# IMU_Project.net
KiCad netlist of a schematic drawn in Altium Designer
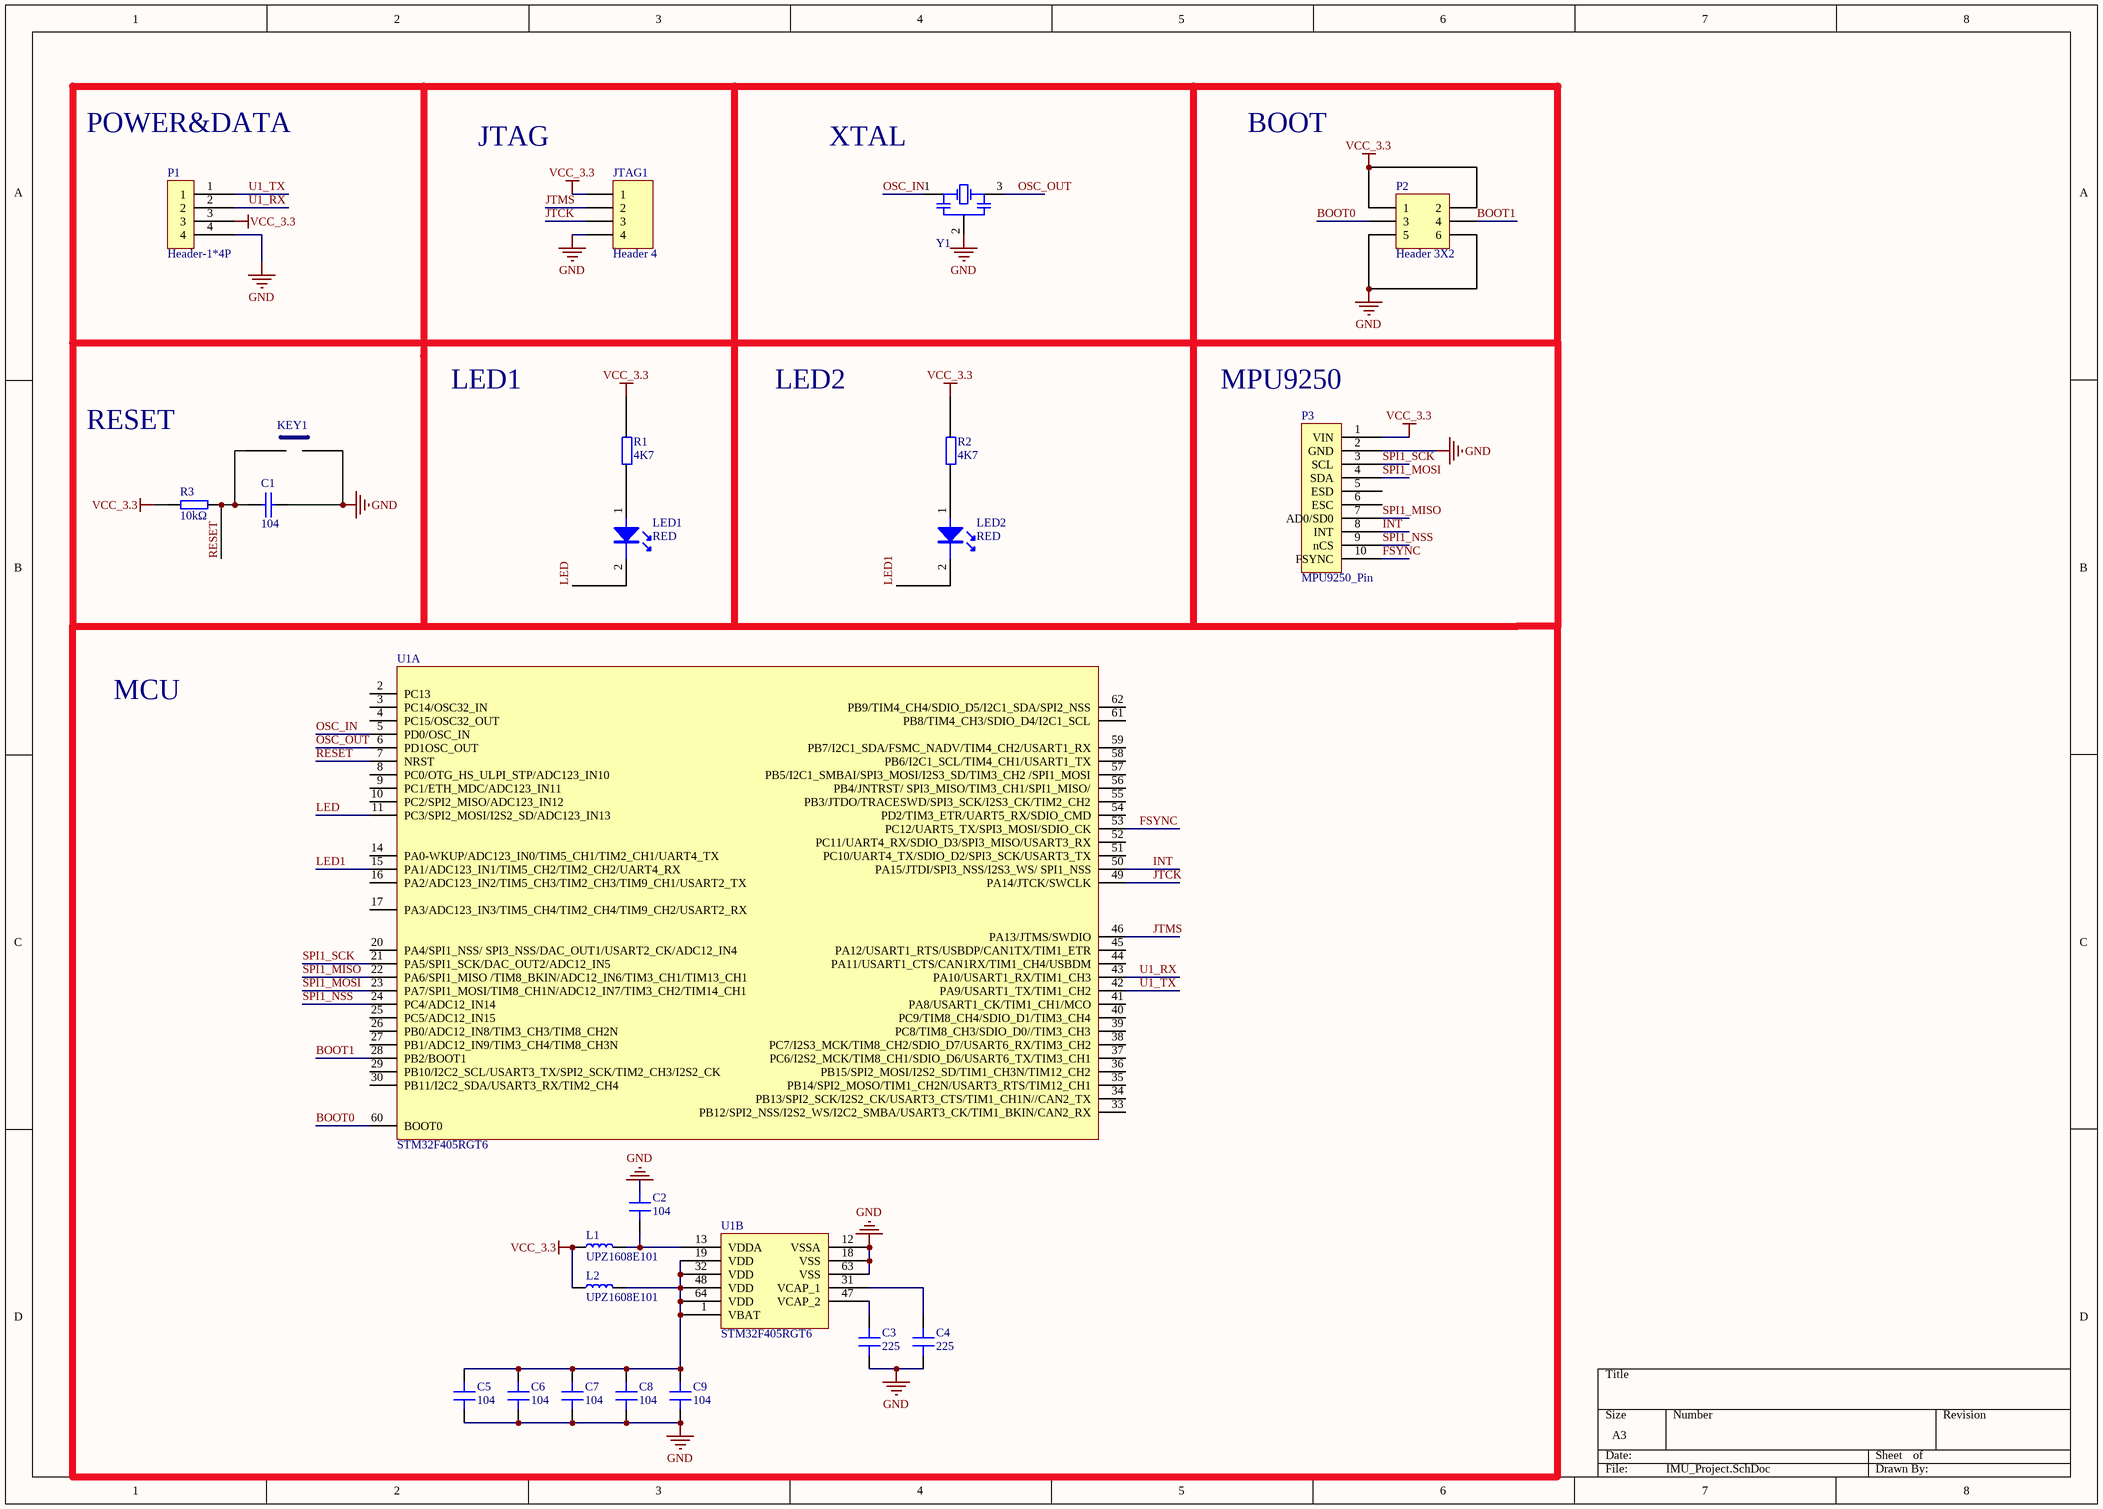
[diagram p0: IMU_Project.SchDoc]

(export (version "E")
  (design (tool "Eeschema 10.0.6"))
  (components
    (comp (ref "C1") (value "104") (footprint "C0603") (libsource (lib "main") (part "C0603")))
    (comp (ref "C2")
      (value "104")
      (footprint "C0603/1608")
      (description "陶瓷电容")
      (libsource (lib "WMJ2019_Devices") (part "陶瓷电容"))
    )
    (comp (ref "C3")
      (value "225")
      (footprint "C0603/1608")
      (description "陶瓷电容")
      (libsource (lib "WMJ2019_Devices") (part "陶瓷电容"))
    )
    (comp (ref "C4")
      (value "225")
      (footprint "C0603/1608")
      (description "陶瓷电容")
      (libsource (lib "WMJ2019_Devices") (part "陶瓷电容"))
    )
    (comp (ref "C5")
      (value "104")
      (footprint "C0603/1608")
      (description "陶瓷电容")
      (libsource (lib "WMJ2019_Devices") (part "陶瓷电容"))
    )
    (comp (ref "C6")
      (value "104")
      (footprint "C0603/1608")
      (description "陶瓷电容")
      (libsource (lib "WMJ2019_Devices") (part "陶瓷电容"))
    )
    (comp (ref "C7")
      (value "104")
      (footprint "C0603/1608")
      (description "陶瓷电容")
      (libsource (lib "WMJ2019_Devices") (part "陶瓷电容"))
    )
    (comp (ref "C8")
      (value "104")
      (footprint "C0603/1608")
      (description "陶瓷电容")
      (libsource (lib "WMJ2019_Devices") (part "陶瓷电容"))
    )
    (comp (ref "C9")
      (value "104")
      (footprint "C0603/1608")
      (description "陶瓷电容")
      (libsource (lib "WMJ2019_Devices") (part "陶瓷电容"))
    )
    (comp (ref "JTAG1")
      (value "Header 4")
      (footprint "Header1*4_XH2.54_zhi")
      (description "Header, 4-Pin")
      (fields (field (name "PUBLISHER") "Altium Limited"))
      (libsource (lib "Miscellaneous Connectors") (part "Header 4"))
    )
    (comp (ref "KEY1") (value "KEY2") (footprint "KEY_RESET") (libsource (lib "library-1") (part "KEY")))
    (comp (ref "L1")
      (value "UPZ1608E101")
      (footprint "L0603/1608")
      (description "贴片磁珠")
      (libsource (lib "WMJ2019_Devices") (part "磁珠"))
    )
    (comp (ref "L2")
      (value "UPZ1608E101")
      (footprint "L0603/1608")
      (description "贴片磁珠")
      (libsource (lib "WMJ2019_Devices") (part "磁珠"))
    )
    (comp (ref "LED1")
      (value "LED RED")
      (footprint "LED0603")
      (fields (field (name "COLOR") "RED"))
      (libsource (lib "Rescue") (part "LED"))
    )
    (comp (ref "LED2")
      (value "LED RED")
      (footprint "LED0603")
      (fields (field (name "COLOR") "RED"))
      (libsource (lib "Rescue") (part "LED"))
    )
    (comp (ref "P1")
      (value "Header-1*4P")
      (footprint "Header1*4_XH2.54_Lie")
      (description "单排4P排针")
      (libsource (lib "WMJ2019_Connectors") (part "Header-1*4P"))
    )
    (comp (ref "P2")
      (value "Header 3X2")
      (footprint "BOOT")
      (description "Header, 3-Pin, Dual row")
      (fields (field (name "PUBLISHER") "Altium Limited"))
      (libsource (lib "PCB_Project") (part "Header 3X2"))
    )
    (comp (ref "P3")
      (value "MPU9250_Pin")
      (footprint "MPU9250_Pin")
      (libsource (lib "MPU9250") (part "MPU9250_Pin"))
    )
    (comp (ref "R1") (value "4K7") (footprint "R0603") (libsource (lib "Rescue") (part "Resistor")))
    (comp (ref "R2") (value "4K7") (footprint "R0603") (libsource (lib "Rescue") (part "Resistor")))
    (comp (ref "R3") (value "10kΩ") (footprint "R0603") (libsource (lib "main") (part "RES_WYN")))
    (comp (ref "U1")
      (value "STM32F405RGT6")
      (footprint "LQFP64")
      (description "微控制器STM32F405RGT6")
      (libsource (lib "WMJ2019_MCU") (part "STM32F405RGT6"))
    )
    (comp (ref "Y1")
      (value "Crystal_Cap")
      (footprint "XTAL-3213")
      (fields (field (name "PUBLISHER") "Altium Limited"))
      (libsource (lib "chassis_PCB_Project") (part "Crystal_Cap"))
    )
  )
  (nets
    (net (code "1") (name "/BOOT0") (class "Default")
      (node (ref "P2") (pin "3") (pinfunction "3_3") (pintype "passive"))
      (node (ref "U1") (pin "60") (pinfunction "BOOT0_60") (pintype "passive"))
    )
    (net (code "2") (name "/BOOT1") (class "Default")
      (node (ref "P2") (pin "4") (pinfunction "4_4") (pintype "passive"))
      (node (ref "U1") (pin "28") (pinfunction "PB2/BOOT1_28") (pintype "passive"))
    )
    (net (code "3") (name "/FSYNC") (class "Default")
      (node (ref "P3") (pin "10") (pinfunction "FSYNC_10") (pintype "passive"))
      (node (ref "U1") (pin "53") (pinfunction "PC12/UART5_TX/SPI3_MOSI/SDIO_CK_53") (pintype "passive"))
    )
    (net (code "4") (name "/INT") (class "Default")
      (node (ref "P3") (pin "8") (pinfunction "INT_8") (pintype "passive"))
      (node (ref "U1") (pin "50") (pinfunction "PA15/JTDI/SPI3_NSS/I2S3_WS/_SPI1_NSS_50") (pintype "passive"))
    )
    (net (code "5") (name "/JTCK") (class "Default")
      (node (ref "JTAG1") (pin "3") (pinfunction "3_3") (pintype "passive"))
      (node (ref "U1") (pin "49") (pinfunction "PA14/JTCK/SWCLK_49") (pintype "passive"))
    )
    (net (code "6") (name "/JTMS") (class "Default")
      (node (ref "JTAG1") (pin "2") (pinfunction "2_2") (pintype "passive"))
      (node (ref "U1") (pin "46") (pinfunction "PA13/JTMS/SWDIO_46") (pintype "passive"))
    )
    (net (code "7") (name "/LED") (class "Default")
      (node (ref "LED1") (pin "2") (pinfunction "K_2") (pintype "passive"))
      (node (ref "U1") (pin "11") (pinfunction "PC3/SPI2_MOSI/I2S2_SD/ADC123_IN13_11") (pintype "passive"))
    )
    (net (code "8") (name "/LED1") (class "Default")
      (node (ref "LED2") (pin "2") (pinfunction "K_2") (pintype "passive"))
      (node (ref "U1") (pin "15") (pinfunction "PA1/ADC123_IN1/TIM5_CH2/TIM2_CH2/UART4_RX_15") (pintype "passive"))
    )
    (net (code "9") (name "/OSC_IN") (class "Default")
      (node (ref "U1") (pin "5") (pinfunction "PD0/OSC_IN_5") (pintype "passive"))
      (node (ref "Y1") (pin "1") (pinfunction "OSC1_1") (pintype "passive"))
    )
    (net (code "10") (name "/OSC_OUT") (class "Default")
      (node (ref "U1") (pin "6") (pinfunction "PD1OSC_OUT_6") (pintype "passive"))
      (node (ref "Y1") (pin "3") (pinfunction "OSC3_3") (pintype "passive"))
    )
    (net (code "11") (name "/RESET") (class "Default")
      (node (ref "C1") (pin "1") (pintype "passive"))
      (node (ref "KEY1") (pin "2") (pinfunction "2_2") (pintype "passive"))
      (node (ref "R3") (pin "1") (pinfunction "1_1") (pintype "passive"))
      (node (ref "U1") (pin "7") (pinfunction "NRST_7") (pintype "passive"))
    )
    (net (code "12") (name "/SPI1_MISO") (class "Default")
      (node (ref "P3") (pin "7") (pinfunction "AD0/SD0_7") (pintype "passive"))
      (node (ref "U1") (pin "22") (pinfunction "PA6/SPI1_MISO_/TIM8_BKIN/ADC12_IN6/TIM3_CH1/TIM13_CH1_22") (pintype "passive"))
    )
    (net (code "13") (name "/SPI1_MOSI") (class "Default")
      (node (ref "P3") (pin "4") (pinfunction "SDA_4") (pintype "passive"))
      (node (ref "U1") (pin "23") (pinfunction "PA7/SPI1_MOSI/TIM8_CH1N/ADC12_IN7/TIM3_CH2/TIM14_CH1_23") (pintype "passive"))
    )
    (net (code "14") (name "/SPI1_NSS") (class "Default")
      (node (ref "P3") (pin "9") (pinfunction "nCS_9") (pintype "passive"))
      (node (ref "U1") (pin "24") (pinfunction "PC4/ADC12_IN14_24") (pintype "passive"))
    )
    (net (code "15") (name "/SPI1_SCK") (class "Default")
      (node (ref "P3") (pin "3") (pinfunction "SCL_3") (pintype "passive"))
      (node (ref "U1") (pin "21") (pinfunction "PA5/SPI1_SCK/DAC_OUT2/ADC12_IN5_21") (pintype "passive"))
    )
    (net (code "16") (name "/U1_RX") (class "Default")
      (node (ref "P1") (pin "2") (pinfunction "2_2") (pintype "passive"))
      (node (ref "U1") (pin "43") (pinfunction "PA10/USART1_RX/TIM1_CH3_43") (pintype "passive"))
    )
    (net (code "17") (name "/U1_TX") (class "Default")
      (node (ref "P1") (pin "1") (pinfunction "1_1") (pintype "passive"))
      (node (ref "U1") (pin "42") (pinfunction "PA9/USART1_TX/TIM1_CH2_42") (pintype "passive"))
    )
    (net (code "18") (name "GND") (class "Default")
      (node (ref "C1") (pin "2") (pintype "passive"))
      (node (ref "C2") (pin "2") (pintype "passive"))
      (node (ref "C3") (pin "1") (pintype "passive"))
      (node (ref "C4") (pin "1") (pintype "passive"))
      (node (ref "C5") (pin "1") (pintype "passive"))
      (node (ref "C6") (pin "1") (pintype "passive"))
      (node (ref "C7") (pin "1") (pintype "passive"))
      (node (ref "C8") (pin "1") (pintype "passive"))
      (node (ref "C9") (pin "1") (pintype "passive"))
      (node (ref "JTAG1") (pin "4") (pinfunction "4_4") (pintype "passive"))
      (node (ref "KEY1") (pin "1") (pinfunction "1_1") (pintype "passive"))
      (node (ref "P1") (pin "4") (pinfunction "4_4") (pintype "passive"))
      (node (ref "P2") (pin "5") (pinfunction "5_5") (pintype "passive"))
      (node (ref "P2") (pin "6") (pinfunction "6_6") (pintype "passive"))
      (node (ref "P3") (pin "2") (pinfunction "GND_2") (pintype "passive"))
      (node (ref "U1") (pin "12") (pinfunction "VSSA_12") (pintype "passive"))
      (node (ref "U1") (pin "18") (pinfunction "VSS_18") (pintype "passive"))
      (node (ref "U1") (pin "63") (pinfunction "VSS_63") (pintype "passive"))
      (node (ref "Y1") (pin "2") (pinfunction "OSC2_2") (pintype "passive"))
    )
    (net (code "19") (name "Net-(LED1-A)") (class "Default")
      (node (ref "LED1") (pin "1") (pinfunction "A_1") (pintype "passive"))
      (node (ref "R1") (pin "1") (pintype "passive"))
    )
    (net (code "20") (name "Net-(LED2-A)") (class "Default")
      (node (ref "LED2") (pin "1") (pinfunction "A_1") (pintype "passive"))
      (node (ref "R2") (pin "1") (pintype "passive"))
    )
    (net (code "21") (name "Net-(U1B-VBAT)") (class "Default")
      (node (ref "C5") (pin "2") (pintype "passive"))
      (node (ref "C6") (pin "2") (pintype "passive"))
      (node (ref "C7") (pin "2") (pintype "passive"))
      (node (ref "C8") (pin "2") (pintype "passive"))
      (node (ref "C9") (pin "2") (pintype "passive"))
      (node (ref "L2") (pin "2") (pinfunction "2_2") (pintype "passive"))
      (node (ref "U1") (pin "1") (pinfunction "VBAT_1") (pintype "passive"))
      (node (ref "U1") (pin "19") (pinfunction "VDD_19") (pintype "passive"))
      (node (ref "U1") (pin "32") (pinfunction "VDD_32") (pintype "passive"))
      (node (ref "U1") (pin "48") (pinfunction "VDD_48") (pintype "passive"))
      (node (ref "U1") (pin "64") (pinfunction "VDD_64") (pintype "passive"))
    )
    (net (code "22") (name "Net-(U1B-VCAP_1)") (class "Default")
      (node (ref "C4") (pin "2") (pintype "passive"))
      (node (ref "U1") (pin "31") (pinfunction "VCAP_1_31") (pintype "passive"))
    )
    (net (code "23") (name "Net-(U1B-VCAP_2)") (class "Default")
      (node (ref "C3") (pin "2") (pintype "passive"))
      (node (ref "U1") (pin "47") (pinfunction "VCAP_2_47") (pintype "passive"))
    )
    (net (code "24") (name "Net-(U1B-VDDA)") (class "Default")
      (node (ref "C2") (pin "1") (pintype "passive"))
      (node (ref "L1") (pin "2") (pinfunction "2_2") (pintype "passive"))
      (node (ref "U1") (pin "13") (pinfunction "VDDA_13") (pintype "passive"))
    )
    (net (code "25") (name "VCC_3.3") (class "Default")
      (node (ref "JTAG1") (pin "1") (pinfunction "1_1") (pintype "passive"))
      (node (ref "L1") (pin "1") (pinfunction "1_1") (pintype "passive"))
      (node (ref "L2") (pin "1") (pinfunction "1_1") (pintype "passive"))
      (node (ref "P1") (pin "3") (pinfunction "3_3") (pintype "passive"))
      (node (ref "P2") (pin "1") (pinfunction "1_1") (pintype "passive"))
      (node (ref "P2") (pin "2") (pinfunction "2_2") (pintype "passive"))
      (node (ref "P3") (pin "1") (pinfunction "VIN_1") (pintype "passive"))
      (node (ref "R1") (pin "2") (pintype "passive"))
      (node (ref "R2") (pin "2") (pintype "passive"))
      (node (ref "R3") (pin "2") (pinfunction "2_2") (pintype "passive"))
    )
    (net (code "26") (name "unconnected-(P3-ESC-Pad6)") (class "Default")
      (node (ref "P3") (pin "6") (pinfunction "ESC_6") (pintype "passive"))
    )
    (net (code "27") (name "unconnected-(P3-ESD-Pad5)") (class "Default")
      (node (ref "P3") (pin "5") (pinfunction "ESD_5") (pintype "passive"))
    )
    (net (code "28") (name "unconnected-(U1A-PA0-WKUP{slash}ADC123_IN0{slash}TIM5_CH1{slash}TIM2_CH1{slash}UART4_TX-Pad14)") (class "Default")
      (node (ref "U1") (pin "14") (pinfunction "PA0-WKUP/ADC123_IN0/TIM5_CH1/TIM2_CH1/UART4_TX_14") (pintype "passive"))
    )
    (net (code "29") (name "unconnected-(U1A-PA2{slash}ADC123_IN2{slash}TIM5_CH3{slash}TIM2_CH3{slash}TIM9_CH1{slash}USART2_TX-Pad16)") (class "Default")
      (node (ref "U1") (pin "16") (pinfunction "PA2/ADC123_IN2/TIM5_CH3/TIM2_CH3/TIM9_CH1/USART2_TX_16") (pintype "passive"))
    )
    (net (code "30") (name "unconnected-(U1A-PA3{slash}ADC123_IN3{slash}TIM5_CH4{slash}TIM2_CH4{slash}TIM9_CH2{slash}USART2_RX-Pad17)") (class "Default")
      (node (ref "U1") (pin "17") (pinfunction "PA3/ADC123_IN3/TIM5_CH4/TIM2_CH4/TIM9_CH2/USART2_RX_17") (pintype "passive"))
    )
    (net (code "31") (name "unconnected-(U1A-PA4{slash}SPI1_NSS{slash}_SPI3_NSS{slash}DAC_OUT1{slash}USART2_CK{slash}ADC12_IN4-Pad20)") (class "Default")
      (node (ref "U1") (pin "20") (pinfunction "PA4/SPI1_NSS/_SPI3_NSS/DAC_OUT1/USART2_CK/ADC12_IN4_20") (pintype "passive"))
    )
    (net (code "32") (name "unconnected-(U1A-PA8{slash}USART1_CK{slash}TIM1_CH1{slash}MCO-Pad41)") (class "Default")
      (node (ref "U1") (pin "41") (pinfunction "PA8/USART1_CK/TIM1_CH1/MCO_41") (pintype "passive"))
    )
    (net (code "33") (name "unconnected-(U1A-PA11{slash}USART1_CTS{slash}CAN1RX{slash}TIM1_CH4{slash}USBDM-Pad44)") (class "Default")
      (node (ref "U1") (pin "44") (pinfunction "PA11/USART1_CTS/CAN1RX/TIM1_CH4/USBDM_44") (pintype "passive"))
    )
    (net (code "34") (name "unconnected-(U1A-PA12{slash}USART1_RTS{slash}USBDP{slash}CAN1TX{slash}TIM1_ETR-Pad45)") (class "Default")
      (node (ref "U1") (pin "45") (pinfunction "PA12/USART1_RTS/USBDP/CAN1TX/TIM1_ETR_45") (pintype "passive"))
    )
    (net (code "35") (name "unconnected-(U1A-PB0{slash}ADC12_IN8{slash}TIM3_CH3{slash}TIM8_CH2N-Pad26)") (class "Default")
      (node (ref "U1") (pin "26") (pinfunction "PB0/ADC12_IN8/TIM3_CH3/TIM8_CH2N_26") (pintype "passive"))
    )
    (net (code "36") (name "unconnected-(U1A-PB1{slash}ADC12_IN9{slash}TIM3_CH4{slash}TIM8_CH3N-Pad27)") (class "Default")
      (node (ref "U1") (pin "27") (pinfunction "PB1/ADC12_IN9/TIM3_CH4/TIM8_CH3N_27") (pintype "passive"))
    )
    (net (code "37") (name "unconnected-(U1A-PB3{slash}JTDO{slash}TRACESWD{slash}SPI3_SCK{slash}I2S3_CK{slash}TIM2_CH2-Pad55)") (class "Default")
      (node (ref "U1") (pin "55") (pinfunction "PB3/JTDO/TRACESWD/SPI3_SCK/I2S3_CK/TIM2_CH2_55") (pintype "passive"))
    )
    (net (code "38") (name "unconnected-(U1A-PB4{slash}JNTRST{slash}_SPI3_MISO{slash}TIM3_CH1{slash}SPI1_MISO{slash}-Pad56)") (class "Default")
      (node (ref "U1") (pin "56") (pinfunction "PB4/JNTRST/_SPI3_MISO/TIM3_CH1/SPI1_MISO/_56") (pintype "passive"))
    )
    (net (code "39") (name "unconnected-(U1A-PB5{slash}I2C1_SMBAI{slash}SPI3_MOSI{slash}I2S3_SD{slash}TIM3_CH2_{slash}SPI1_MOSI-Pad57)") (class "Default")
      (node (ref "U1") (pin "57") (pinfunction "PB5/I2C1_SMBAI/SPI3_MOSI/I2S3_SD/TIM3_CH2_/SPI1_MOSI_57") (pintype "passive"))
    )
    (net (code "40") (name "unconnected-(U1A-PB6{slash}I2C1_SCL{slash}TIM4_CH1{slash}USART1_TX-Pad58)") (class "Default")
      (node (ref "U1") (pin "58") (pinfunction "PB6/I2C1_SCL/TIM4_CH1/USART1_TX_58") (pintype "passive"))
    )
    (net (code "41") (name "unconnected-(U1A-PB7{slash}I2C1_SDA{slash}FSMC_NADV{slash}TIM4_CH2{slash}USART1_RX-Pad59)") (class "Default")
      (node (ref "U1") (pin "59") (pinfunction "PB7/I2C1_SDA/FSMC_NADV/TIM4_CH2/USART1_RX_59") (pintype "passive"))
    )
    (net (code "42") (name "unconnected-(U1A-PB8{slash}TIM4_CH3{slash}SDIO_D4{slash}I2C1_SCL-Pad61)") (class "Default")
      (node (ref "U1") (pin "61") (pinfunction "PB8/TIM4_CH3/SDIO_D4/I2C1_SCL_61") (pintype "passive"))
    )
    (net (code "43") (name "unconnected-(U1A-PB9{slash}TIM4_CH4{slash}SDIO_D5{slash}I2C1_SDA{slash}SPI2_NSS-Pad62)") (class "Default")
      (node (ref "U1") (pin "62") (pinfunction "PB9/TIM4_CH4/SDIO_D5/I2C1_SDA/SPI2_NSS_62") (pintype "passive"))
    )
    (net (code "44") (name "unconnected-(U1A-PB10{slash}I2C2_SCL{slash}USART3_TX{slash}SPI2_SCK{slash}TIM2_CH3{slash}I2S2_CK-Pad29)") (class "Default")
      (node (ref "U1") (pin "29") (pinfunction "PB10/I2C2_SCL/USART3_TX/SPI2_SCK/TIM2_CH3/I2S2_CK_29") (pintype "passive"))
    )
    (net (code "45") (name "unconnected-(U1A-PB11{slash}I2C2_SDA{slash}USART3_RX{slash}TIM2_CH4-Pad30)") (class "Default")
      (node (ref "U1") (pin "30") (pinfunction "PB11/I2C2_SDA/USART3_RX/TIM2_CH4_30") (pintype "passive"))
    )
    (net (code "46") (name "unconnected-(U1A-PB12{slash}SPI2_NSS{slash}I2S2_WS{slash}I2C2_SMBA{slash}USART3_CK{slash}TIM1_BKIN{slash}CAN2_RX-Pad33)") (class "Default")
      (node (ref "U1") (pin "33") (pinfunction "PB12/SPI2_NSS/I2S2_WS/I2C2_SMBA/USART3_CK/TIM1_BKIN/CAN2_RX_33") (pintype "passive"))
    )
    (net (code "47") (name "unconnected-(U1A-PB13{slash}SPI2_SCK{slash}I2S2_CK{slash}USART3_CTS{slash}TIM1_CH1N{slash}{slash}CAN2_TX-Pad34)") (class "Default")
      (node (ref "U1") (pin "34") (pinfunction "PB13/SPI2_SCK/I2S2_CK/USART3_CTS/TIM1_CH1N//CAN2_TX_34") (pintype "passive"))
    )
    (net (code "48") (name "unconnected-(U1A-PB14{slash}SPI2_MOSO{slash}TIM1_CH2N{slash}USART3_RTS{slash}TIM12_CH1-Pad35)") (class "Default")
      (node (ref "U1") (pin "35") (pinfunction "PB14/SPI2_MOSO/TIM1_CH2N/USART3_RTS/TIM12_CH1_35") (pintype "passive"))
    )
    (net (code "49") (name "unconnected-(U1A-PB15{slash}SPI2_MOSI{slash}I2S2_SD{slash}TIM1_CH3N{slash}TIM12_CH2-Pad36)") (class "Default")
      (node (ref "U1") (pin "36") (pinfunction "PB15/SPI2_MOSI/I2S2_SD/TIM1_CH3N/TIM12_CH2_36") (pintype "passive"))
    )
    (net (code "50") (name "unconnected-(U1A-PC0{slash}OTG_HS_ULPI_STP{slash}ADC123_IN10-Pad8)") (class "Default")
      (node (ref "U1") (pin "8") (pinfunction "PC0/OTG_HS_ULPI_STP/ADC123_IN10_8") (pintype "passive"))
    )
    (net (code "51") (name "unconnected-(U1A-PC1{slash}ETH_MDC{slash}ADC123_IN11-Pad9)") (class "Default")
      (node (ref "U1") (pin "9") (pinfunction "PC1/ETH_MDC/ADC123_IN11_9") (pintype "passive"))
    )
    (net (code "52") (name "unconnected-(U1A-PC2{slash}SPI2_MISO{slash}ADC123_IN12-Pad10)") (class "Default")
      (node (ref "U1") (pin "10") (pinfunction "PC2/SPI2_MISO/ADC123_IN12_10") (pintype "passive"))
    )
    (net (code "53") (name "unconnected-(U1A-PC5{slash}ADC12_IN15-Pad25)") (class "Default")
      (node (ref "U1") (pin "25") (pinfunction "PC5/ADC12_IN15_25") (pintype "passive"))
    )
    (net (code "54") (name "unconnected-(U1A-PC6{slash}I2S2_MCK{slash}TIM8_CH1{slash}SDIO_D6{slash}USART6_TX{slash}TIM3_CH1-Pad37)") (class "Default")
      (node (ref "U1") (pin "37") (pinfunction "PC6/I2S2_MCK/TIM8_CH1/SDIO_D6/USART6_TX/TIM3_CH1_37") (pintype "passive"))
    )
    (net (code "55") (name "unconnected-(U1A-PC7{slash}I2S3_MCK{slash}TIM8_CH2{slash}SDIO_D7{slash}USART6_RX{slash}TIM3_CH2-Pad38)") (class "Default")
      (node (ref "U1") (pin "38") (pinfunction "PC7/I2S3_MCK/TIM8_CH2/SDIO_D7/USART6_RX/TIM3_CH2_38") (pintype "passive"))
    )
    (net (code "56") (name "unconnected-(U1A-PC8{slash}TIM8_CH3{slash}SDIO_D0{slash}{slash}TIM3_CH3-Pad39)") (class "Default")
      (node (ref "U1") (pin "39") (pinfunction "PC8/TIM8_CH3/SDIO_D0//TIM3_CH3_39") (pintype "passive"))
    )
    (net (code "57") (name "unconnected-(U1A-PC9{slash}TIM8_CH4{slash}SDIO_D1{slash}TIM3_CH4-Pad40)") (class "Default")
      (node (ref "U1") (pin "40") (pinfunction "PC9/TIM8_CH4/SDIO_D1/TIM3_CH4_40") (pintype "passive"))
    )
    (net (code "58") (name "unconnected-(U1A-PC10{slash}UART4_TX{slash}SDIO_D2{slash}SPI3_SCK{slash}USART3_TX-Pad51)") (class "Default")
      (node (ref "U1") (pin "51") (pinfunction "PC10/UART4_TX/SDIO_D2/SPI3_SCK/USART3_TX_51") (pintype "passive"))
    )
    (net (code "59") (name "unconnected-(U1A-PC11{slash}UART4_RX{slash}SDIO_D3{slash}SPI3_MISO{slash}USART3_RX-Pad52)") (class "Default")
      (node (ref "U1") (pin "52") (pinfunction "PC11/UART4_RX/SDIO_D3/SPI3_MISO/USART3_RX_52") (pintype "passive"))
    )
    (net (code "60") (name "unconnected-(U1A-PC13-Pad2)") (class "Default")
      (node (ref "U1") (pin "2") (pinfunction "PC13_2") (pintype "passive"))
    )
    (net (code "61") (name "unconnected-(U1A-PC14{slash}OSC32_IN-Pad3)") (class "Default")
      (node (ref "U1") (pin "3") (pinfunction "PC14/OSC32_IN_3") (pintype "passive"))
    )
    (net (code "62") (name "unconnected-(U1A-PC15{slash}OSC32_OUT-Pad4)") (class "Default")
      (node (ref "U1") (pin "4") (pinfunction "PC15/OSC32_OUT_4") (pintype "passive"))
    )
    (net (code "63") (name "unconnected-(U1A-PD2{slash}TIM3_ETR{slash}UART5_RX{slash}SDIO_CMD-Pad54)") (class "Default")
      (node (ref "U1") (pin "54") (pinfunction "PD2/TIM3_ETR/UART5_RX/SDIO_CMD_54") (pintype "passive"))
    )
  )
)
